# STM32F103C8-core.net
KiCad netlist of a schematic drawn in Altium Designer
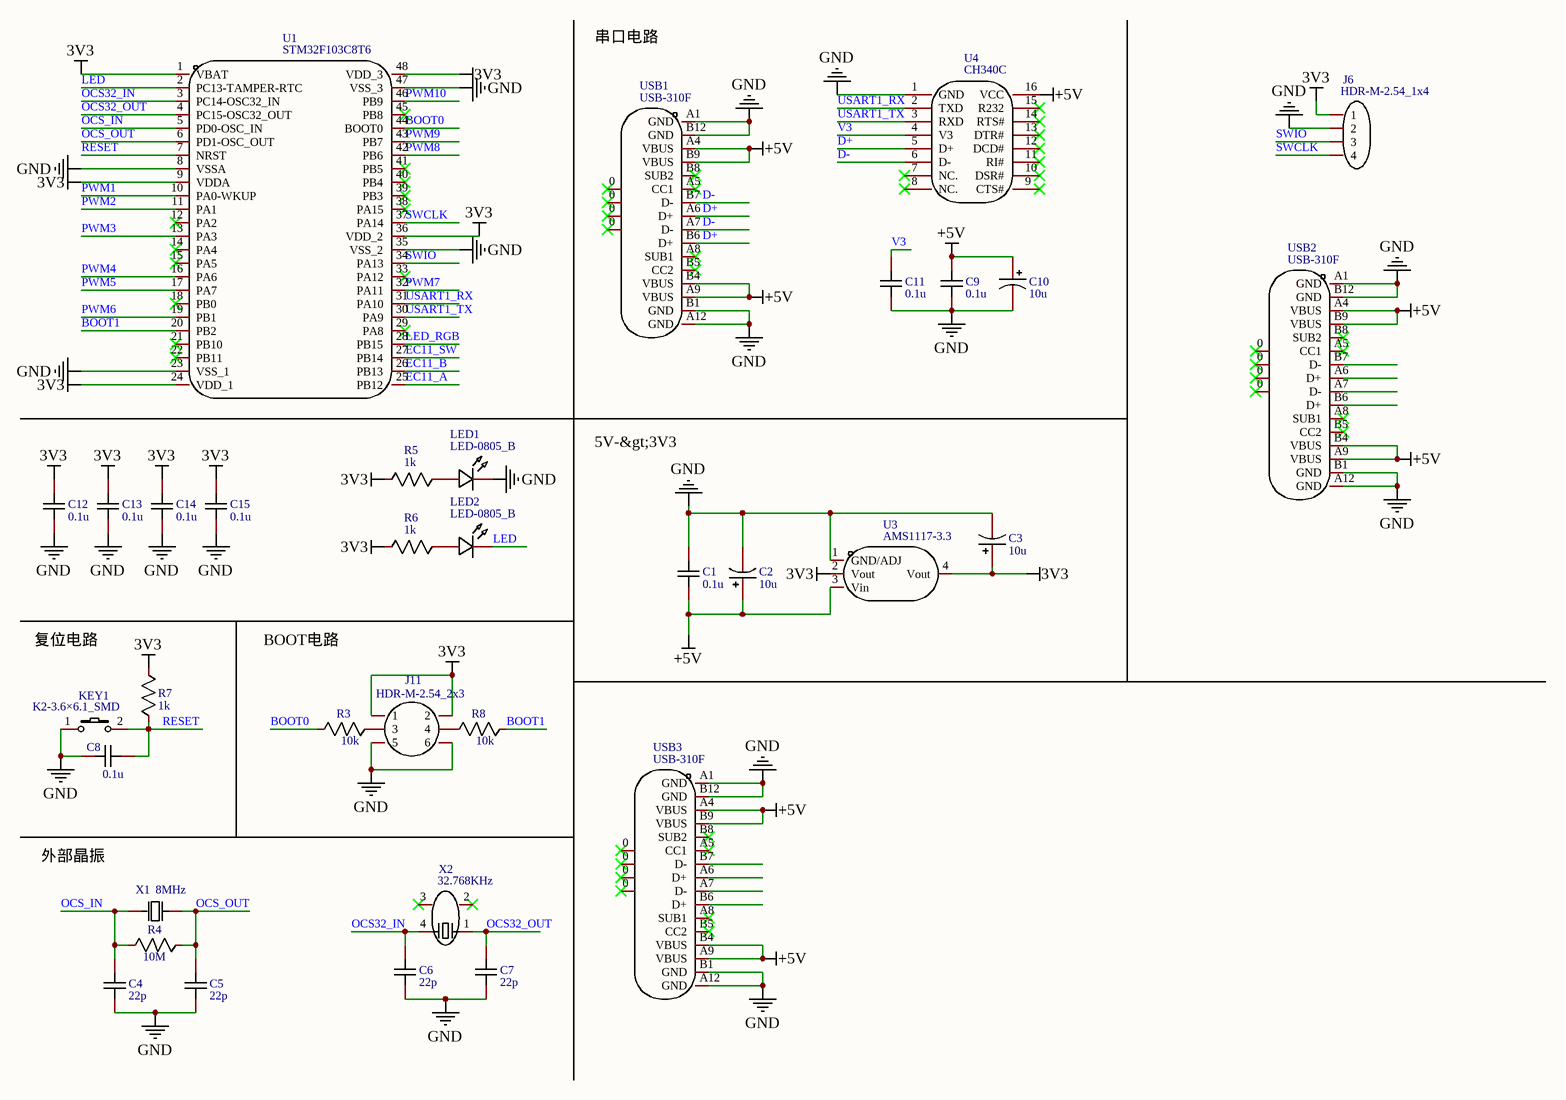
[diagram p0: STM32F103C8-core.schdoc]

(export (version "E")
  (design (tool "Eeschema 10.0.6"))
  (components
    (comp (ref "C1")
      (value "0.1u")
      (footprint "C0805")
      (fields (field (name "NAME") "0.1u"))
      (libsource (lib "altium-import") (part "root_1_0.1u_"))
    )
    (comp (ref "C2")
      (value "10u")
      (footprint "CASE-A_3216")
      (fields (field (name "NAME") "10u"))
      (libsource (lib "altium-import") (part "root_1_10u_"))
    )
    (comp (ref "C3")
      (value "10u")
      (footprint "CASE-A_3216")
      (fields (field (name "NAME") "10u"))
      (libsource (lib "altium-import") (part "root_1_10u_"))
    )
    (comp (ref "C4")
      (value "22p")
      (footprint "C0805")
      (fields (field (name "NAME") "22p"))
      (libsource (lib "altium-import") (part "root_1_22p_"))
    )
    (comp (ref "C5")
      (value "22p")
      (footprint "C0805")
      (fields (field (name "NAME") "22p"))
      (libsource (lib "altium-import") (part "root_1_22p_"))
    )
    (comp (ref "C6")
      (value "22p")
      (footprint "C0805")
      (fields (field (name "NAME") "22p"))
      (libsource (lib "altium-import") (part "root_1_22p_"))
    )
    (comp (ref "C7")
      (value "22p")
      (footprint "C0805")
      (fields (field (name "NAME") "22p"))
      (libsource (lib "altium-import") (part "root_1_22p_"))
    )
    (comp (ref "C8")
      (value "0.1u")
      (footprint "C0805")
      (fields (field (name "NAME") "0.1u"))
      (libsource (lib "altium-import") (part "root_2_0.1u_"))
    )
    (comp (ref "C9")
      (value "0.1u")
      (footprint "C0805")
      (fields (field (name "NAME") "0.1u"))
      (libsource (lib "altium-import") (part "root_1_0.1u_"))
    )
    (comp (ref "C10")
      (value "10u")
      (footprint "CASE-A_3216")
      (fields (field (name "NAME") "10u"))
      (libsource (lib "altium-import") (part "root_3_10u_"))
    )
    (comp (ref "C11")
      (value "0.1u")
      (footprint "C0805")
      (fields (field (name "NAME") "0.1u"))
      (libsource (lib "altium-import") (part "root_1_0.1u_"))
    )
    (comp (ref "C12")
      (value "0.1u")
      (footprint "C0805")
      (fields (field (name "NAME") "0.1u"))
      (libsource (lib "altium-import") (part "root_1_0.1u_"))
    )
    (comp (ref "C13")
      (value "0.1u")
      (footprint "C0805")
      (fields (field (name "NAME") "0.1u"))
      (libsource (lib "altium-import") (part "root_1_0.1u_"))
    )
    (comp (ref "C14")
      (value "0.1u")
      (footprint "C0805")
      (fields (field (name "NAME") "0.1u"))
      (libsource (lib "altium-import") (part "root_1_0.1u_"))
    )
    (comp (ref "C15")
      (value "0.1u")
      (footprint "C0805")
      (fields (field (name "NAME") "0.1u"))
      (libsource (lib "altium-import") (part "root_1_0.1u_"))
    )
    (comp (ref "J6")
      (value "HDR-M-2.54_1x4")
      (footprint "HDR-M-2.54_1X4")
      (fields (field (name "NAME") "HDR-M-2.54_1x4"))
      (libsource (lib "altium-import") (part "root_0_HDR-M-2.54_1x4_"))
    )
    (comp (ref "J11")
      (value "HDR-M-2.54_2x3")
      (footprint "HDR-M-2.54_2X3")
      (fields (field (name "NAME") "HDR-M-2.54_2x3"))
      (libsource (lib "altium-import") (part "root_0_HDR-M-2.54_2x3_"))
    )
    (comp (ref "KEY1")
      (value "K2-3.6×6.1_SMD")
      (footprint "KEY-SMD_2P-L6.2-W3.6-LS8.0")
      (fields (field (name "NAME") "K2-3.6×6.1_SMD") (field (name "MANUFACTURER PART") "K2-1107ST-A4SW-06"))
      (libsource (lib "altium-import") (part "root_0_K2-1107ST-A4SW-06_"))
    )
    (comp (ref "LED1")
      (value "LED-0805_B")
      (footprint "LED0805_BLUE")
      (fields
        (field (name "NAME") "LED-0805_B")
        (field (name "MANUFACTURER") "方舟 ARKLED")
        (field (name "MANUFACTURER PART") "D-B080508B1-KS2")
      )
      (libsource (lib "altium-import") (part "root_0_D-B080508B1-KS2_"))
    )
    (comp (ref "LED2")
      (value "LED-0805_B")
      (footprint "LED0805_BLUE")
      (fields
        (field (name "NAME") "LED-0805_B")
        (field (name "MANUFACTURER") "方舟 ARKLED")
        (field (name "MANUFACTURER PART") "D-B080508B1-KS2")
      )
      (libsource (lib "altium-import") (part "root_0_D-B080508B1-KS2_"))
    )
    (comp (ref "R3")
      (value "10k")
      (footprint "R0805")
      (fields (field (name "NAME") "10k"))
      (libsource (lib "altium-import") (part "root_0_10k_"))
    )
    (comp (ref "R4")
      (value "10M")
      (footprint "R0805")
      (fields (field (name "NAME") "10M"))
      (libsource (lib "altium-import") (part "root_0_10M_"))
    )
    (comp (ref "R5")
      (value "1k")
      (footprint "R0805")
      (fields (field (name "NAME") "1k"))
      (libsource (lib "altium-import") (part "root_0_1k_"))
    )
    (comp (ref "R6")
      (value "1k")
      (footprint "R0805")
      (fields (field (name "NAME") "1k"))
      (libsource (lib "altium-import") (part "root_0_1k_"))
    )
    (comp (ref "R7")
      (value "1k")
      (footprint "R0805")
      (fields (field (name "NAME") "1k"))
      (libsource (lib "altium-import") (part "root_1_1k_"))
    )
    (comp (ref "R8")
      (value "10k")
      (footprint "R0805")
      (fields (field (name "NAME") "10k"))
      (libsource (lib "altium-import") (part "root_0_10k_"))
    )
    (comp (ref "U1")
      (value "STM32F103C8T6")
      (footprint "LQFP-48_L7.0-W7.0-P0.50-LS9.0-BL")
      (fields (field (name "NAME") "STM32F103C8T6") (field (name "MANUFACTURER") "STMicroelectronics"))
      (libsource (lib "altium-import") (part "root_0_STM32F103C8T6_"))
    )
    (comp (ref "U3")
      (value "AMS1117-3.3")
      (footprint "SOT-223-3_L6.5-W3.4-P2.30-LS7.0-BR")
      (fields (field (name "NAME") "AMS1117-3.3") (field (name "MANUFACTURER") "AMS"))
      (libsource (lib "altium-import") (part "root_0_AMS1117-3.3_"))
    )
    (comp (ref "U4")
      (value "CH340C")
      (footprint "SOP-16_L10.0-W3.9-P1.27-LS6.0-BL")
      (fields (field (name "NAME") "CH340C") (field (name "MANUFACTURER") "WCH"))
      (libsource (lib "altium-import") (part "root_0_CH340C_"))
    )
    (comp (ref "USB1")
      (value "USB-310F")
      (footprint "USB-C-SMD_20P-P0.50-L6.5-W8.9")
      (fields (field (name "NAME") "USB-310F") (field (name "MANUFACTURER") "HOOYA"))
      (libsource (lib "altium-import") (part "root_0_USB-310F_"))
    )
    (comp (ref "USB2")
      (value "USB-310F")
      (footprint "USB-C-SMD_20P-P0.50-L6.5-W8.9")
      (fields (field (name "NAME") "USB-310F") (field (name "MANUFACTURER") "HOOYA"))
      (libsource (lib "altium-import") (part "root_0_USB-310F_"))
    )
    (comp (ref "USB3")
      (value "USB-310F")
      (footprint "USB-C-SMD_20P-P0.50-L6.5-W8.9")
      (fields (field (name "NAME") "USB-310F") (field (name "MANUFACTURER") "HOOYA"))
      (libsource (lib "altium-import") (part "root_0_USB-310F_"))
    )
    (comp (ref "X1")
      (value "8MHz")
      (footprint "OSC-TH_L11.1-W4.7-P4.88")
      (description "频率:8MHz;频率公差:±20ppm;频率稳定度:±30ppm;负载电容:16pF;")
      (fields
        (field (name "NAME") "8MHz")
        (field (name "MANUFACTURER") "JYJE(晶友嘉)")
        (field (name "MANUFACTURER PART") "S1C80000VWGAC")
      )
      (libsource (lib "altium-import") (part "root_0_S1C80000VWGAC_"))
    )
    (comp (ref "X2")
      (value "32.768KHz")
      (footprint "MC-306_4P-L8.0-W3.2-P5.5-BL")
      (fields
        (field (name "NAME") "32.768KHz")
        (field (name "MANUFACTURER PART") "Q13MC3061000300")
        (field (name "MANUFACTURER") "EPSON")
      )
      (libsource (lib "altium-import") (part "root_1_Q13MC3061000300_"))
    )
  )
  (nets
    (net (code "1") (name "+5V") (class "Default")
      (node (ref "C1") (pin "1") (pinfunction "1_1") (pintype "passive"))
      (node (ref "C10") (pin "1") (pinfunction "1_1") (pintype "passive"))
      (node (ref "C2") (pin "1") (pinfunction "1_1") (pintype "passive"))
      (node (ref "C9") (pin "2") (pinfunction "2_2") (pintype "passive"))
      (node (ref "U3") (pin "3") (pinfunction "Vin_3") (pintype "passive"))
      (node (ref "U4") (pin "16") (pinfunction "VCC_16") (pintype "passive"))
      (node (ref "USB1") (pin "A4") (pinfunction "VBUS_A4") (pintype "passive"))
      (node (ref "USB1") (pin "A9") (pinfunction "VBUS_A9") (pintype "passive"))
      (node (ref "USB1") (pin "B4") (pinfunction "VBUS_B4") (pintype "passive"))
      (node (ref "USB1") (pin "B9") (pinfunction "VBUS_B9") (pintype "passive"))
      (node (ref "USB2") (pin "A4") (pinfunction "VBUS_A4") (pintype "passive"))
      (node (ref "USB2") (pin "A9") (pinfunction "VBUS_A9") (pintype "passive"))
      (node (ref "USB2") (pin "B4") (pinfunction "VBUS_B4") (pintype "passive"))
      (node (ref "USB2") (pin "B9") (pinfunction "VBUS_B9") (pintype "passive"))
      (node (ref "USB3") (pin "A4") (pinfunction "VBUS_A4") (pintype "passive"))
      (node (ref "USB3") (pin "A9") (pinfunction "VBUS_A9") (pintype "passive"))
      (node (ref "USB3") (pin "B4") (pinfunction "VBUS_B4") (pintype "passive"))
      (node (ref "USB3") (pin "B9") (pinfunction "VBUS_B9") (pintype "passive"))
    )
    (net (code "2") (name "/BOOT0") (class "Default")
      (node (ref "R3") (pin "1") (pinfunction "1_1") (pintype "passive"))
      (node (ref "U1") (pin "44") (pinfunction "BOOT0_44") (pintype "passive"))
    )
    (net (code "3") (name "/BOOT1") (class "Default")
      (node (ref "R8") (pin "2") (pinfunction "2_2") (pintype "passive"))
      (node (ref "U1") (pin "20") (pinfunction "PB2_20") (pintype "passive"))
    )
    (net (code "4") (name "/D+") (class "Default")
      (node (ref "U4") (pin "5") (pinfunction "D+_5") (pintype "passive"))
      (node (ref "USB1") (pin "A6") (pinfunction "D+_A6") (pintype "passive"))
      (node (ref "USB1") (pin "B6") (pinfunction "D+_B6") (pintype "passive"))
    )
    (net (code "5") (name "/D-") (class "Default")
      (node (ref "U4") (pin "6") (pinfunction "D-_6") (pintype "passive"))
      (node (ref "USB1") (pin "A7") (pinfunction "D-_A7") (pintype "passive"))
      (node (ref "USB1") (pin "B7") (pinfunction "D-_B7") (pintype "passive"))
    )
    (net (code "6") (name "/EC11_A") (class "Default")
      (node (ref "U1") (pin "25") (pinfunction "PB12_25") (pintype "passive"))
    )
    (net (code "7") (name "/EC11_B") (class "Default")
      (node (ref "U1") (pin "26") (pinfunction "PB13_26") (pintype "passive"))
    )
    (net (code "8") (name "/EC11_SW") (class "Default")
      (node (ref "U1") (pin "27") (pinfunction "PB14_27") (pintype "passive"))
    )
    (net (code "9") (name "/LED") (class "Default")
      (node (ref "LED2") (pin "2") (pinfunction "2_2") (pintype "passive"))
      (node (ref "U1") (pin "2") (pinfunction "PC13-TAMPER-RTC_2") (pintype "passive"))
    )
    (net (code "10") (name "/LED_RGB") (class "Default")
      (node (ref "U1") (pin "28") (pinfunction "PB15_28") (pintype "passive"))
    )
    (net (code "11") (name "/OCS32_IN") (class "Default")
      (node (ref "C6") (pin "2") (pinfunction "2_2") (pintype "passive"))
      (node (ref "U1") (pin "3") (pinfunction "PC14-OSC32_IN_3") (pintype "passive"))
      (node (ref "X2") (pin "4") (pinfunction "4_4") (pintype "passive"))
    )
    (net (code "12") (name "/OCS32_OUT") (class "Default")
      (node (ref "C7") (pin "2") (pinfunction "2_2") (pintype "passive"))
      (node (ref "U1") (pin "4") (pinfunction "PC15-OSC32_OUT_4") (pintype "passive"))
      (node (ref "X2") (pin "1") (pinfunction "1_1") (pintype "passive"))
    )
    (net (code "13") (name "/OCS_IN") (class "Default")
      (node (ref "C4") (pin "2") (pinfunction "2_2") (pintype "passive"))
      (node (ref "R4") (pin "1") (pinfunction "1_1") (pintype "passive"))
      (node (ref "U1") (pin "5") (pinfunction "PD0-OSC_IN_5") (pintype "passive"))
      (node (ref "X1") (pin "1") (pinfunction "OSC1_1") (pintype "passive"))
    )
    (net (code "14") (name "/OCS_OUT") (class "Default")
      (node (ref "C5") (pin "2") (pinfunction "2_2") (pintype "passive"))
      (node (ref "R4") (pin "2") (pinfunction "2_2") (pintype "passive"))
      (node (ref "U1") (pin "6") (pinfunction "PD1-OSC_OUT_6") (pintype "passive"))
      (node (ref "X1") (pin "2") (pinfunction "OSC2_2") (pintype "passive"))
    )
    (net (code "15") (name "/PWM1") (class "Default")
      (node (ref "U1") (pin "10") (pinfunction "PA0-WKUP_10") (pintype "passive"))
    )
    (net (code "16") (name "/PWM2") (class "Default")
      (node (ref "U1") (pin "11") (pinfunction "PA1_11") (pintype "passive"))
    )
    (net (code "17") (name "/PWM3") (class "Default")
      (node (ref "U1") (pin "13") (pinfunction "PA3_13") (pintype "passive"))
    )
    (net (code "18") (name "/PWM4") (class "Default")
      (node (ref "U1") (pin "16") (pinfunction "PA6_16") (pintype "passive"))
    )
    (net (code "19") (name "/PWM5") (class "Default")
      (node (ref "U1") (pin "17") (pinfunction "PA7_17") (pintype "passive"))
    )
    (net (code "20") (name "/PWM6") (class "Default")
      (node (ref "U1") (pin "19") (pinfunction "PB1_19") (pintype "passive"))
    )
    (net (code "21") (name "/PWM7") (class "Default")
      (node (ref "U1") (pin "32") (pinfunction "PA11_32") (pintype "passive"))
    )
    (net (code "22") (name "/PWM8") (class "Default")
      (node (ref "U1") (pin "42") (pinfunction "PB6_42") (pintype "passive"))
    )
    (net (code "23") (name "/PWM9") (class "Default")
      (node (ref "U1") (pin "43") (pinfunction "PB7_43") (pintype "passive"))
    )
    (net (code "24") (name "/PWM10") (class "Default")
      (node (ref "U1") (pin "46") (pinfunction "PB9_46") (pintype "passive"))
    )
    (net (code "25") (name "/RESET") (class "Default")
      (node (ref "C8") (pin "1") (pinfunction "1_1") (pintype "passive"))
      (node (ref "KEY1") (pin "2") (pinfunction "2_2") (pintype "passive"))
      (node (ref "R7") (pin "1") (pinfunction "1_1") (pintype "passive"))
      (node (ref "U1") (pin "7") (pinfunction "NRST_7") (pintype "passive"))
    )
    (net (code "26") (name "/SWCLK") (class "Default")
      (node (ref "J6") (pin "4") (pinfunction "4_4") (pintype "passive"))
      (node (ref "U1") (pin "37") (pinfunction "PA14_37") (pintype "passive"))
    )
    (net (code "27") (name "/SWIO") (class "Default")
      (node (ref "J6") (pin "3") (pinfunction "3_3") (pintype "passive"))
      (node (ref "U1") (pin "34") (pinfunction "PA13_34") (pintype "passive"))
    )
    (net (code "28") (name "/USART1_RX") (class "Default")
      (node (ref "U1") (pin "31") (pinfunction "PA10_31") (pintype "passive"))
      (node (ref "U4") (pin "2") (pinfunction "TXD_2") (pintype "passive"))
    )
    (net (code "29") (name "/USART1_TX") (class "Default")
      (node (ref "U1") (pin "30") (pinfunction "PA9_30") (pintype "passive"))
      (node (ref "U4") (pin "3") (pinfunction "RXD_3") (pintype "passive"))
    )
    (net (code "30") (name "/V3") (class "Default")
      (node (ref "C11") (pin "2") (pinfunction "2_2") (pintype "passive"))
      (node (ref "U4") (pin "4") (pinfunction "V3_4") (pintype "passive"))
    )
    (net (code "31") (name "3V3") (class "Default")
      (node (ref "C12") (pin "2") (pinfunction "2_2") (pintype "passive"))
      (node (ref "C13") (pin "2") (pinfunction "2_2") (pintype "passive"))
      (node (ref "C14") (pin "2") (pinfunction "2_2") (pintype "passive"))
      (node (ref "C15") (pin "2") (pinfunction "2_2") (pintype "passive"))
      (node (ref "C3") (pin "1") (pinfunction "1_1") (pintype "passive"))
      (node (ref "J11") (pin "1") (pinfunction "1_1") (pintype "passive"))
      (node (ref "J11") (pin "2") (pinfunction "2_2") (pintype "passive"))
      (node (ref "J6") (pin "1") (pinfunction "1_1") (pintype "passive"))
      (node (ref "R5") (pin "1") (pinfunction "1_1") (pintype "passive"))
      (node (ref "R6") (pin "1") (pinfunction "1_1") (pintype "passive"))
      (node (ref "R7") (pin "2") (pinfunction "2_2") (pintype "passive"))
      (node (ref "U1") (pin "1") (pinfunction "VBAT_1") (pintype "passive"))
      (node (ref "U1") (pin "24") (pinfunction "VDD_1_24") (pintype "passive"))
      (node (ref "U1") (pin "36") (pinfunction "VDD_2_36") (pintype "passive"))
      (node (ref "U1") (pin "48") (pinfunction "VDD_3_48") (pintype "passive"))
      (node (ref "U1") (pin "9") (pinfunction "VDDA_9") (pintype "passive"))
      (node (ref "U3") (pin "2") (pinfunction "Vout_2") (pintype "passive"))
      (node (ref "U3") (pin "4") (pinfunction "Vout_4") (pintype "passive"))
    )
    (net (code "32") (name "GND") (class "Default")
      (node (ref "C1") (pin "2") (pinfunction "2_2") (pintype "passive"))
      (node (ref "C10") (pin "2") (pinfunction "2_2") (pintype "passive"))
      (node (ref "C11") (pin "1") (pinfunction "1_1") (pintype "passive"))
      (node (ref "C12") (pin "1") (pinfunction "1_1") (pintype "passive"))
      (node (ref "C13") (pin "1") (pinfunction "1_1") (pintype "passive"))
      (node (ref "C14") (pin "1") (pinfunction "1_1") (pintype "passive"))
      (node (ref "C15") (pin "1") (pinfunction "1_1") (pintype "passive"))
      (node (ref "C2") (pin "2") (pinfunction "2_2") (pintype "passive"))
      (node (ref "C3") (pin "2") (pinfunction "2_2") (pintype "passive"))
      (node (ref "C4") (pin "1") (pinfunction "1_1") (pintype "passive"))
      (node (ref "C5") (pin "1") (pinfunction "1_1") (pintype "passive"))
      (node (ref "C6") (pin "1") (pinfunction "1_1") (pintype "passive"))
      (node (ref "C7") (pin "1") (pinfunction "1_1") (pintype "passive"))
      (node (ref "C8") (pin "2") (pinfunction "2_2") (pintype "passive"))
      (node (ref "C9") (pin "1") (pinfunction "1_1") (pintype "passive"))
      (node (ref "J11") (pin "5") (pinfunction "5_5") (pintype "passive"))
      (node (ref "J11") (pin "6") (pinfunction "6_6") (pintype "passive"))
      (node (ref "J6") (pin "2") (pinfunction "2_2") (pintype "passive"))
      (node (ref "KEY1") (pin "1") (pinfunction "1_1") (pintype "passive"))
      (node (ref "LED1") (pin "2") (pinfunction "2_2") (pintype "passive"))
      (node (ref "U1") (pin "23") (pinfunction "VSS_1_23") (pintype "passive"))
      (node (ref "U1") (pin "35") (pinfunction "VSS_2_35") (pintype "passive"))
      (node (ref "U1") (pin "47") (pinfunction "VSS_3_47") (pintype "passive"))
      (node (ref "U1") (pin "8") (pinfunction "VSSA_8") (pintype "passive"))
      (node (ref "U3") (pin "1") (pinfunction "GND/ADJ_1") (pintype "passive"))
      (node (ref "U4") (pin "1") (pinfunction "GND_1") (pintype "passive"))
      (node (ref "USB1") (pin "A1") (pinfunction "GND_A1") (pintype "passive"))
      (node (ref "USB1") (pin "A12") (pinfunction "GND_A12") (pintype "passive"))
      (node (ref "USB1") (pin "B1") (pinfunction "GND_B1") (pintype "passive"))
      (node (ref "USB1") (pin "B12") (pinfunction "GND_B12") (pintype "passive"))
      (node (ref "USB2") (pin "A1") (pinfunction "GND_A1") (pintype "passive"))
      (node (ref "USB2") (pin "A12") (pinfunction "GND_A12") (pintype "passive"))
      (node (ref "USB2") (pin "B1") (pinfunction "GND_B1") (pintype "passive"))
      (node (ref "USB2") (pin "B12") (pinfunction "GND_B12") (pintype "passive"))
      (node (ref "USB3") (pin "A1") (pinfunction "GND_A1") (pintype "passive"))
      (node (ref "USB3") (pin "A12") (pinfunction "GND_A12") (pintype "passive"))
      (node (ref "USB3") (pin "B1") (pinfunction "GND_B1") (pintype "passive"))
      (node (ref "USB3") (pin "B12") (pinfunction "GND_B12") (pintype "passive"))
    )
    (net (code "33") (name "Net-(J11-Pad3)") (class "Default")
      (node (ref "J11") (pin "3") (pinfunction "3_3") (pintype "passive"))
      (node (ref "R3") (pin "2") (pinfunction "2_2") (pintype "passive"))
    )
    (net (code "34") (name "Net-(J11-Pad4)") (class "Default")
      (node (ref "J11") (pin "4") (pinfunction "4_4") (pintype "passive"))
      (node (ref "R8") (pin "1") (pinfunction "1_1") (pintype "passive"))
    )
    (net (code "35") (name "Net-(LED1-Pad1)") (class "Default")
      (node (ref "LED1") (pin "1") (pinfunction "1_1") (pintype "passive"))
      (node (ref "R5") (pin "2") (pinfunction "2_2") (pintype "passive"))
    )
    (net (code "36") (name "Net-(LED2-Pad1)") (class "Default")
      (node (ref "LED2") (pin "1") (pinfunction "1_1") (pintype "passive"))
      (node (ref "R6") (pin "2") (pinfunction "2_2") (pintype "passive"))
    )
    (net (code "37") (name "unconnected-(U1-PA2-Pad12)") (class "Default")
      (node (ref "U1") (pin "12") (pinfunction "PA2_12") (pintype "passive+no_connect"))
    )
    (net (code "38") (name "unconnected-(U1-PA4-Pad14)") (class "Default")
      (node (ref "U1") (pin "14") (pinfunction "PA4_14") (pintype "passive+no_connect"))
    )
    (net (code "39") (name "unconnected-(U1-PA5-Pad15)") (class "Default")
      (node (ref "U1") (pin "15") (pinfunction "PA5_15") (pintype "passive+no_connect"))
    )
    (net (code "40") (name "unconnected-(U1-PA8-Pad29)") (class "Default")
      (node (ref "U1") (pin "29") (pinfunction "PA8_29") (pintype "passive+no_connect"))
    )
    (net (code "41") (name "unconnected-(U1-PA12-Pad33)") (class "Default")
      (node (ref "U1") (pin "33") (pinfunction "PA12_33") (pintype "passive+no_connect"))
    )
    (net (code "42") (name "unconnected-(U1-PA15-Pad38)") (class "Default")
      (node (ref "U1") (pin "38") (pinfunction "PA15_38") (pintype "passive+no_connect"))
    )
    (net (code "43") (name "unconnected-(U1-PB0-Pad18)") (class "Default")
      (node (ref "U1") (pin "18") (pinfunction "PB0_18") (pintype "passive+no_connect"))
    )
    (net (code "44") (name "unconnected-(U1-PB3-Pad39)") (class "Default")
      (node (ref "U1") (pin "39") (pinfunction "PB3_39") (pintype "passive+no_connect"))
    )
    (net (code "45") (name "unconnected-(U1-PB4-Pad40)") (class "Default")
      (node (ref "U1") (pin "40") (pinfunction "PB4_40") (pintype "passive+no_connect"))
    )
    (net (code "46") (name "unconnected-(U1-PB5-Pad41)") (class "Default")
      (node (ref "U1") (pin "41") (pinfunction "PB5_41") (pintype "passive+no_connect"))
    )
    (net (code "47") (name "unconnected-(U1-PB8-Pad45)") (class "Default")
      (node (ref "U1") (pin "45") (pinfunction "PB8_45") (pintype "passive+no_connect"))
    )
    (net (code "48") (name "unconnected-(U1-PB10-Pad21)") (class "Default")
      (node (ref "U1") (pin "21") (pinfunction "PB10_21") (pintype "passive+no_connect"))
    )
    (net (code "49") (name "unconnected-(U1-PB11-Pad22)") (class "Default")
      (node (ref "U1") (pin "22") (pinfunction "PB11_22") (pintype "passive+no_connect"))
    )
    (net (code "50") (name "unconnected-(U4-CTS#-Pad9)") (class "Default")
      (node (ref "U4") (pin "9") (pinfunction "CTS#_9") (pintype "passive+no_connect"))
    )
    (net (code "51") (name "unconnected-(U4-DCD#-Pad12)") (class "Default")
      (node (ref "U4") (pin "12") (pinfunction "DCD#_12") (pintype "passive+no_connect"))
    )
    (net (code "52") (name "unconnected-(U4-DSR#-Pad10)") (class "Default")
      (node (ref "U4") (pin "10") (pinfunction "DSR#_10") (pintype "passive+no_connect"))
    )
    (net (code "53") (name "unconnected-(U4-DTR#-Pad13)") (class "Default")
      (node (ref "U4") (pin "13") (pinfunction "DTR#_13") (pintype "passive+no_connect"))
    )
    (net (code "54") (name "unconnected-(U4-NC.-Pad7)") (class "Default")
      (node (ref "U4") (pin "7") (pinfunction "NC._7") (pintype "passive+no_connect"))
    )
    (net (code "55") (name "unconnected-(U4-NC.-Pad8)") (class "Default")
      (node (ref "U4") (pin "8") (pinfunction "NC._8") (pintype "passive+no_connect"))
    )
    (net (code "56") (name "unconnected-(U4-R232-Pad15)") (class "Default")
      (node (ref "U4") (pin "15") (pinfunction "R232_15") (pintype "passive+no_connect"))
    )
    (net (code "57") (name "unconnected-(U4-RI#-Pad11)") (class "Default")
      (node (ref "U4") (pin "11") (pinfunction "RI#_11") (pintype "passive+no_connect"))
    )
    (net (code "58") (name "unconnected-(U4-RTS#-Pad14)") (class "Default")
      (node (ref "U4") (pin "14") (pinfunction "RTS#_14") (pintype "passive+no_connect"))
    )
    (net (code "59") (name "unconnected-(USB1-CC1-PadA5)") (class "Default")
      (node (ref "USB1") (pin "A5") (pinfunction "CC1_A5") (pintype "passive+no_connect"))
    )
    (net (code "60") (name "unconnected-(USB1-CC2-PadB5)") (class "Default")
      (node (ref "USB1") (pin "B5") (pinfunction "CC2_B5") (pintype "passive+no_connect"))
    )
    (net (code "61") (name "unconnected-(USB1-Pad0)") (class "Default")
      (node (ref "USB1") (pin "0") (pinfunction "0_0") (pintype "passive+no_connect"))
    )
    (net (code "62") (name "unconnected-(USB1-Pad0)_1") (class "Default")
      (node (ref "USB1") (pin "0") (pinfunction "0_0") (pintype "passive+no_connect"))
    )
    (net (code "63") (name "unconnected-(USB1-Pad0)_2") (class "Default")
      (node (ref "USB1") (pin "0") (pinfunction "0_0") (pintype "passive+no_connect"))
    )
    (net (code "64") (name "unconnected-(USB1-Pad0)_3") (class "Default")
      (node (ref "USB1") (pin "0") (pinfunction "0_0") (pintype "passive+no_connect"))
    )
    (net (code "65") (name "unconnected-(USB1-SUB1-PadA8)") (class "Default")
      (node (ref "USB1") (pin "A8") (pinfunction "SUB1_A8") (pintype "passive+no_connect"))
    )
    (net (code "66") (name "unconnected-(USB1-SUB2-PadB8)") (class "Default")
      (node (ref "USB1") (pin "B8") (pinfunction "SUB2_B8") (pintype "passive+no_connect"))
    )
    (net (code "67") (name "unconnected-(USB2-CC1-PadA5)") (class "Default")
      (node (ref "USB2") (pin "A5") (pinfunction "CC1_A5") (pintype "passive+no_connect"))
    )
    (net (code "68") (name "unconnected-(USB2-CC2-PadB5)") (class "Default")
      (node (ref "USB2") (pin "B5") (pinfunction "CC2_B5") (pintype "passive+no_connect"))
    )
    (net (code "69") (name "unconnected-(USB2-D+-PadA6)") (class "Default")
      (node (ref "USB2") (pin "A6") (pinfunction "D+_A6") (pintype "passive"))
    )
    (net (code "70") (name "unconnected-(USB2-D+-PadB6)") (class "Default")
      (node (ref "USB2") (pin "B6") (pinfunction "D+_B6") (pintype "passive"))
    )
    (net (code "71") (name "unconnected-(USB2-D--PadA7)") (class "Default")
      (node (ref "USB2") (pin "A7") (pinfunction "D-_A7") (pintype "passive"))
    )
    (net (code "72") (name "unconnected-(USB2-D--PadB7)") (class "Default")
      (node (ref "USB2") (pin "B7") (pinfunction "D-_B7") (pintype "passive"))
    )
    (net (code "73") (name "unconnected-(USB2-Pad0)") (class "Default")
      (node (ref "USB2") (pin "0") (pinfunction "0_0") (pintype "passive+no_connect"))
    )
    (net (code "74") (name "unconnected-(USB2-Pad0)_1") (class "Default")
      (node (ref "USB2") (pin "0") (pinfunction "0_0") (pintype "passive+no_connect"))
    )
    (net (code "75") (name "unconnected-(USB2-Pad0)_2") (class "Default")
      (node (ref "USB2") (pin "0") (pinfunction "0_0") (pintype "passive+no_connect"))
    )
    (net (code "76") (name "unconnected-(USB2-Pad0)_3") (class "Default")
      (node (ref "USB2") (pin "0") (pinfunction "0_0") (pintype "passive+no_connect"))
    )
    (net (code "77") (name "unconnected-(USB2-SUB1-PadA8)") (class "Default")
      (node (ref "USB2") (pin "A8") (pinfunction "SUB1_A8") (pintype "passive+no_connect"))
    )
    (net (code "78") (name "unconnected-(USB2-SUB2-PadB8)") (class "Default")
      (node (ref "USB2") (pin "B8") (pinfunction "SUB2_B8") (pintype "passive+no_connect"))
    )
    (net (code "79") (name "unconnected-(USB3-CC1-PadA5)") (class "Default")
      (node (ref "USB3") (pin "A5") (pinfunction "CC1_A5") (pintype "passive+no_connect"))
    )
    (net (code "80") (name "unconnected-(USB3-CC2-PadB5)") (class "Default")
      (node (ref "USB3") (pin "B5") (pinfunction "CC2_B5") (pintype "passive+no_connect"))
    )
    (net (code "81") (name "unconnected-(USB3-D+-PadA6)") (class "Default")
      (node (ref "USB3") (pin "A6") (pinfunction "D+_A6") (pintype "passive"))
    )
    (net (code "82") (name "unconnected-(USB3-D+-PadB6)") (class "Default")
      (node (ref "USB3") (pin "B6") (pinfunction "D+_B6") (pintype "passive"))
    )
    (net (code "83") (name "unconnected-(USB3-D--PadA7)") (class "Default")
      (node (ref "USB3") (pin "A7") (pinfunction "D-_A7") (pintype "passive"))
    )
    (net (code "84") (name "unconnected-(USB3-D--PadB7)") (class "Default")
      (node (ref "USB3") (pin "B7") (pinfunction "D-_B7") (pintype "passive"))
    )
    (net (code "85") (name "unconnected-(USB3-Pad0)") (class "Default")
      (node (ref "USB3") (pin "0") (pinfunction "0_0") (pintype "passive+no_connect"))
    )
    (net (code "86") (name "unconnected-(USB3-Pad0)_1") (class "Default")
      (node (ref "USB3") (pin "0") (pinfunction "0_0") (pintype "passive+no_connect"))
    )
    (net (code "87") (name "unconnected-(USB3-Pad0)_2") (class "Default")
      (node (ref "USB3") (pin "0") (pinfunction "0_0") (pintype "passive+no_connect"))
    )
    (net (code "88") (name "unconnected-(USB3-Pad0)_3") (class "Default")
      (node (ref "USB3") (pin "0") (pinfunction "0_0") (pintype "passive+no_connect"))
    )
    (net (code "89") (name "unconnected-(USB3-SUB1-PadA8)") (class "Default")
      (node (ref "USB3") (pin "A8") (pinfunction "SUB1_A8") (pintype "passive+no_connect"))
    )
    (net (code "90") (name "unconnected-(USB3-SUB2-PadB8)") (class "Default")
      (node (ref "USB3") (pin "B8") (pinfunction "SUB2_B8") (pintype "passive+no_connect"))
    )
    (net (code "91") (name "unconnected-(X2-Pad2)") (class "Default")
      (node (ref "X2") (pin "2") (pinfunction "2_2") (pintype "passive+no_connect"))
    )
    (net (code "92") (name "unconnected-(X2-Pad3)") (class "Default")
      (node (ref "X2") (pin "3") (pinfunction "3_3") (pintype "passive+no_connect"))
    )
  )
)
